# TurntableStrobe.net
KiCad netlist of a schematic drawn in EAGLE
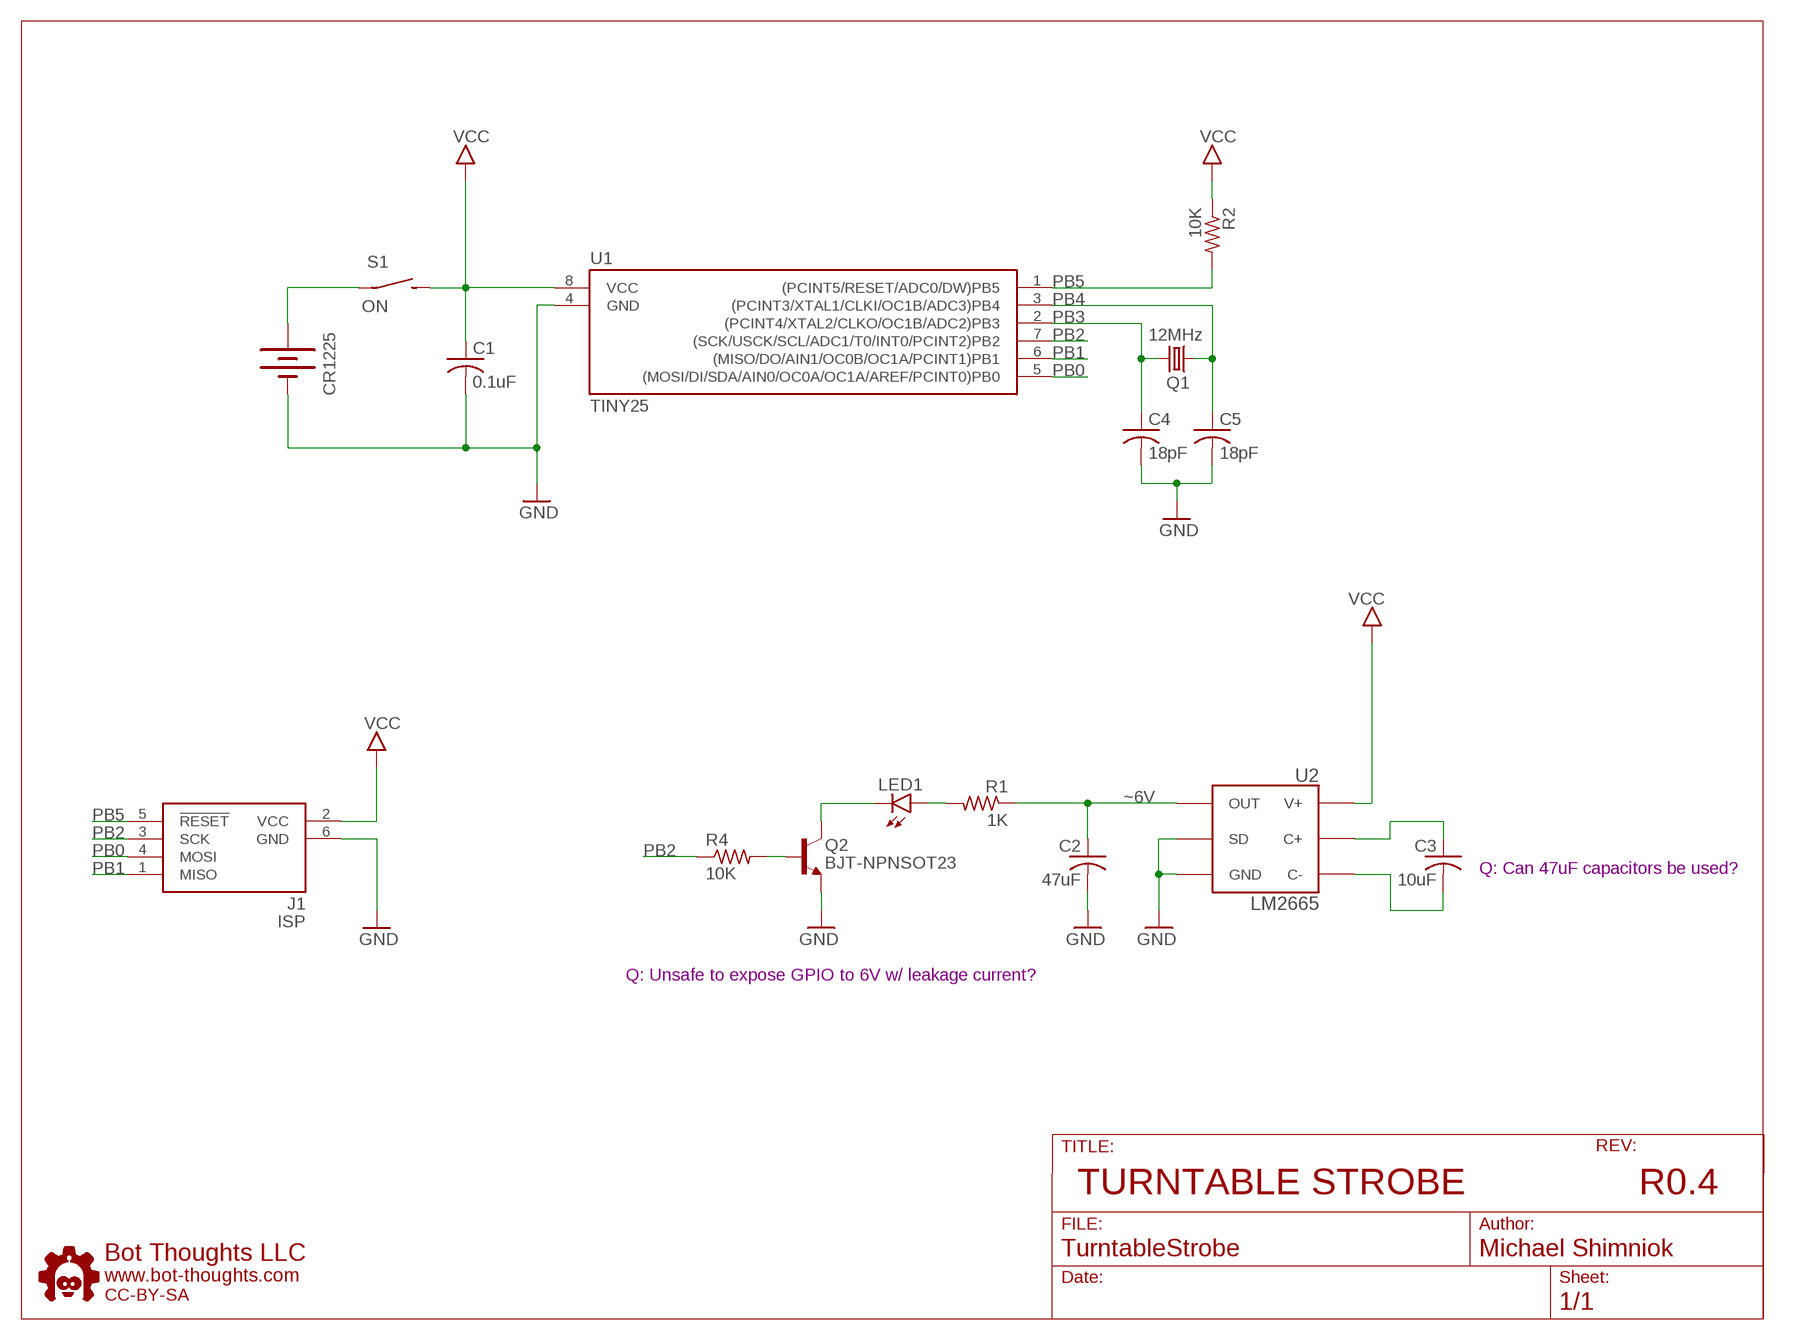
[diagram p0: schematic, sheet 1]

(export (version "E")
  (design (tool "Eeschema 10.0.6"))
  (components
    (comp (ref "C1")
      (value "0.1uF")
      (footprint "eagle-import:C0603")
      (libsource (lib "eagle-import") (part "C-USC0603"))
    )
    (comp (ref "C2")
      (value "47uF")
      (footprint "eagle-import:C0603")
      (libsource (lib "eagle-import") (part "C-USC0603"))
    )
    (comp (ref "C3")
      (value "10uF")
      (footprint "eagle-import:C0603")
      (libsource (lib "eagle-import") (part "C-USC0603"))
    )
    (comp (ref "C4")
      (value "18pF")
      (footprint "eagle-import:C0603")
      (libsource (lib "eagle-import") (part "C-USC0603"))
    )
    (comp (ref "C5")
      (value "18pF")
      (footprint "eagle-import:C0603")
      (libsource (lib "eagle-import") (part "C-USC0603"))
    )
    (comp (ref "CR1225")
      (value "BATTERY12PTH")
      (footprint "eagle-import:BATTCON_12MM_PTH")
      (libsource (lib "eagle-import") (part "BATTERY12PTH"))
    )
    (comp (ref "J1")
      (value "ISP")
      (footprint "eagle-import:2X3_TP")
      (libsource (lib "eagle-import") (part "AVRISP6_TP"))
    )
    (comp (ref "LED1")
      (value "LED5MMRA")
      (footprint "eagle-import:LED5MMRA")
      (libsource (lib "eagle-import") (part "LED5MMRA"))
    )
    (comp (ref "Q1")
      (value "12MHz")
      (footprint "eagle-import:NDK_2PAD_5X3")
      (libsource (lib "eagle-import") (part "CRYSTALNDK5X3"))
    )
    (comp (ref "Q2")
      (value "BJT-NPNSOT23")
      (footprint "eagle-import:SOT-23")
      (libsource (lib "eagle-import") (part "BJT-NPNSOT23"))
    )
    (comp (ref "R1")
      (value "1K")
      (footprint "eagle-import:R0603")
      (libsource (lib "eagle-import") (part "R-US_R0603"))
    )
    (comp (ref "R2")
      (value "10K")
      (footprint "eagle-import:R0603")
      (libsource (lib "eagle-import") (part "R-US_R0603"))
    )
    (comp (ref "R4")
      (value "10K")
      (footprint "eagle-import:R0603")
      (libsource (lib "eagle-import") (part "R-US_R0603"))
    )
    (comp (ref "S1")
      (value "ON")
      (footprint "eagle-import:6MMTACTILE_RECT")
      (libsource (lib "eagle-import") (part "SPST_TAC_RECT1"))
    )
    (comp (ref "U$5")
      (value "BTLOGO-LOGO-SM")
      (footprint "eagle-import:BTLOGOS")
      (libsource (lib "eagle-import") (part "BTLOGO-LOGO-SM"))
    )
    (comp (ref "U1")
      (value "TINY25")
      (footprint "eagle-import:SOIC8N")
      (libsource (lib "eagle-import") (part "TINY25-20SSU"))
    )
    (comp (ref "U2")
      (value "LM2665")
      (footprint "eagle-import:SOT23-6")
      (libsource (lib "eagle-import") (part "LM2665"))
    )
  )
  (nets
    (net (code "1") (name "/PB0") (class "Default")
      (node (ref "J1") (pin "4") (pinfunction "MOSI_4") (pintype "output"))
      (node (ref "U1") (pin "5") (pinfunction "(MOSI/DI/SDA/AIN0/OC0A/OC1A/AREF/PCINT0)PB0_5") (pintype "bidirectional"))
    )
    (net (code "2") (name "/PB1") (class "Default")
      (node (ref "J1") (pin "1") (pinfunction "MISO_1") (pintype "input"))
      (node (ref "U1") (pin "6") (pinfunction "(MISO/DO/AIN1/OC0B/OC1A/PCINT1)PB1_6") (pintype "bidirectional"))
    )
    (net (code "3") (name "/PB2") (class "Default")
      (node (ref "J1") (pin "3") (pinfunction "SCK_3") (pintype "output"))
      (node (ref "R4") (pin "1") (pinfunction "1_1") (pintype "passive"))
      (node (ref "U1") (pin "7") (pinfunction "(SCK/USCK/SCL/ADC1/T0/INT0/PCINT2)PB2_7") (pintype "bidirectional"))
    )
    (net (code "4") (name "/PB3") (class "Default")
      (node (ref "C4") (pin "1") (pinfunction "1_1") (pintype "passive"))
      (node (ref "Q1") (pin "P$2") (pinfunction "2_P$2") (pintype "passive"))
      (node (ref "U1") (pin "2") (pinfunction "(PCINT4/XTAL2/CLKO/OC1B/ADC2)PB3_2") (pintype "bidirectional"))
    )
    (net (code "5") (name "/PB4") (class "Default")
      (node (ref "C5") (pin "1") (pinfunction "1_1") (pintype "passive"))
      (node (ref "Q1") (pin "P$1") (pinfunction "1_P$1") (pintype "passive"))
      (node (ref "U1") (pin "3") (pinfunction "(PCINT3/XTAL1/CLKI/OC1B/ADC3)PB4_3") (pintype "bidirectional"))
    )
    (net (code "6") (name "/PB5") (class "Default")
      (node (ref "J1") (pin "5") (pinfunction "~{RESET}_5") (pintype "output"))
      (node (ref "R2") (pin "2") (pinfunction "2_2") (pintype "passive"))
      (node (ref "U1") (pin "1") (pinfunction "(PCINT5/RESET/ADC0/DW)PB5_1") (pintype "bidirectional"))
    )
    (net (code "7") (name "GND") (class "Default")
      (node (ref "C1") (pin "2") (pinfunction "2_2") (pintype "passive"))
      (node (ref "C2") (pin "2") (pinfunction "2_2") (pintype "passive"))
      (node (ref "C4") (pin "2") (pinfunction "2_2") (pintype "passive"))
      (node (ref "C5") (pin "2") (pinfunction "2_2") (pintype "passive"))
      (node (ref "CR1225") (pin "GND") (pinfunction "-_GND") (pintype "power_in"))
      (node (ref "J1") (pin "6") (pinfunction "GND_6") (pintype "power_in"))
      (node (ref "Q2") (pin "2") (pinfunction "E_2") (pintype "passive"))
      (node (ref "U1") (pin "4") (pinfunction "GND_4") (pintype "power_in"))
      (node (ref "U2") (pin "2") (pinfunction "GND_2") (pintype "bidirectional"))
      (node (ref "U2") (pin "4") (pinfunction "SD_4") (pintype "bidirectional"))
    )
    (net (code "8") (name "Net-(CR1225-+)") (class "Default")
      (node (ref "CR1225") (pin "VCC@1") (pinfunction "+_VCC@1") (pintype "power_in"))
      (node (ref "S1") (pin "P$1") (pinfunction "P_P$1") (pintype "passive"))
    )
    (net (code "9") (name "Net-(LED1-PadA)") (class "Default")
      (node (ref "LED1") (pin "A") (pinfunction "A_A") (pintype "passive"))
      (node (ref "R1") (pin "2") (pinfunction "2_2") (pintype "passive"))
    )
    (net (code "10") (name "Net-(Q2-B)") (class "Default")
      (node (ref "Q2") (pin "3") (pinfunction "B_3") (pintype "passive"))
      (node (ref "R4") (pin "2") (pinfunction "2_2") (pintype "passive"))
    )
    (net (code "11") (name "Net-(Q2-C)") (class "Default")
      (node (ref "LED1") (pin "C") (pinfunction "C_C") (pintype "passive"))
      (node (ref "Q2") (pin "1") (pinfunction "C_1") (pintype "passive"))
    )
    (net (code "12") (name "Net-(U2-C+)") (class "Default")
      (node (ref "C3") (pin "1") (pinfunction "1_1") (pintype "passive"))
      (node (ref "U2") (pin "6") (pinfunction "C+_6") (pintype "bidirectional"))
    )
    (net (code "13") (name "Net-(U2-C-)") (class "Default")
      (node (ref "C3") (pin "2") (pinfunction "2_2") (pintype "passive"))
      (node (ref "U2") (pin "3") (pinfunction "C-_3") (pintype "bidirectional"))
    )
    (net (code "14") (name "Net-(U2-OUT)") (class "Default")
      (node (ref "C2") (pin "1") (pinfunction "1_1") (pintype "passive"))
      (node (ref "R1") (pin "1") (pinfunction "1_1") (pintype "passive"))
      (node (ref "U2") (pin "5") (pinfunction "OUT_5") (pintype "power_in"))
    )
    (net (code "15") (name "VCC") (class "Default")
      (node (ref "C1") (pin "1") (pinfunction "1_1") (pintype "passive"))
      (node (ref "J1") (pin "2") (pinfunction "VCC_2") (pintype "power_in"))
      (node (ref "R2") (pin "1") (pinfunction "1_1") (pintype "passive"))
      (node (ref "S1") (pin "P$2") (pinfunction "S_P$2") (pintype "passive"))
      (node (ref "U1") (pin "8") (pinfunction "VCC_8") (pintype "power_in"))
      (node (ref "U2") (pin "1") (pinfunction "V+_1") (pintype "power_in"))
    )
  )
)
